# TopLevel.net
KiCad netlist of a schematic drawn in Altium Designer
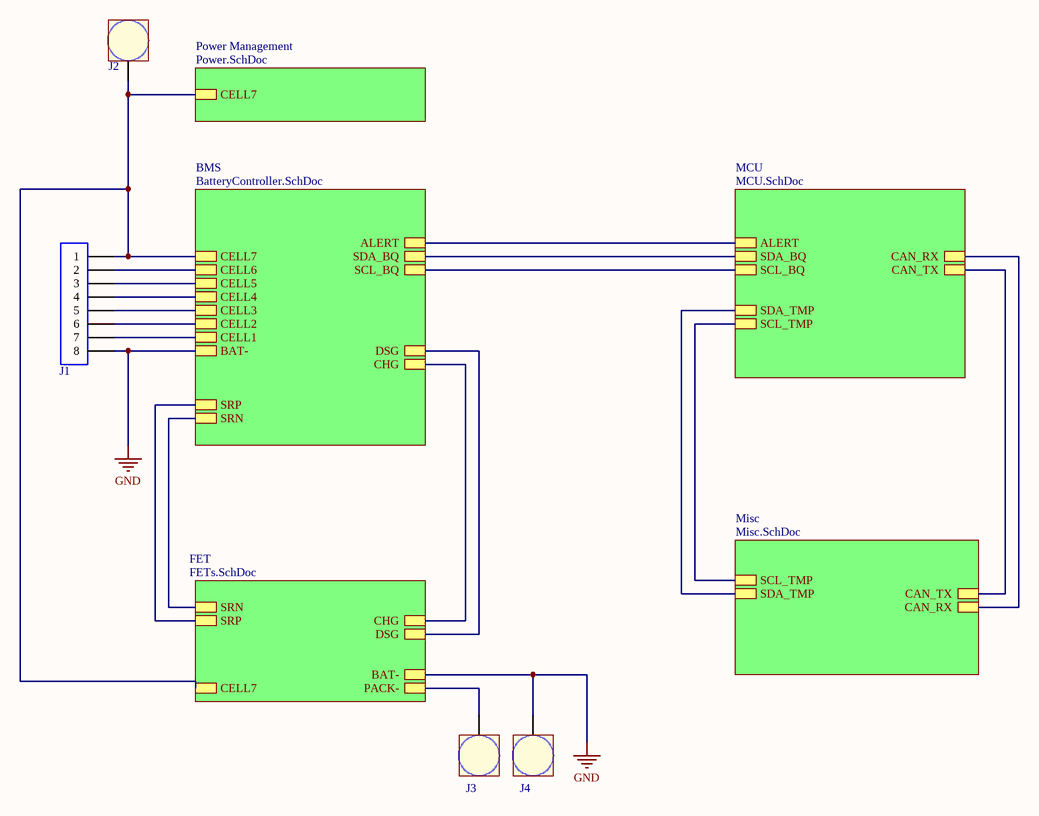
[diagram p0: TopLevel.SchDoc]

(export (version "E")
  (design (tool "Eeschema 10.0.6"))
  (components
    (comp (ref "J1")
      (value "HEADER-MALE-SMT-90C-4COL-2ROW")
      (footprint "0430450810")
      (description "Connector")
      (libsource (lib "Kaptanyums Lib") (part "0430450810"))
    )
    (comp (ref "J2")
      (value "7460305")
      (footprint "7460305")
      (description "Connector")
      (libsource (lib "Kaptanyums Lib") (part "7460305"))
    )
    (comp (ref "J3")
      (value "7460305")
      (footprint "7460305")
      (description "Connector")
      (libsource (lib "") (part "7460305_1"))
    )
    (comp (ref "J4")
      (value "7460305")
      (footprint "7460305")
      (description "Connector")
      (libsource (lib "") (part "7460305_1"))
    )
  )
  (nets
    (net (code "4") (name "/CELL1") (class "Default")
      (node (ref "J1") (pin "7") (pinfunction "7_7") (pintype "passive"))
    )
    (net (code "5") (name "/CELL2") (class "Default")
      (node (ref "J1") (pin "6") (pinfunction "6_6") (pintype "passive"))
    )
    (net (code "6") (name "/CELL3") (class "Default")
      (node (ref "J1") (pin "5") (pinfunction "5_5") (pintype "passive"))
    )
    (net (code "7") (name "/CELL4") (class "Default")
      (node (ref "J1") (pin "4") (pinfunction "4_4") (pintype "passive"))
    )
    (net (code "8") (name "/CELL5") (class "Default")
      (node (ref "J1") (pin "3") (pinfunction "3_3") (pintype "passive"))
    )
    (net (code "9") (name "/CELL6") (class "Default")
      (node (ref "J1") (pin "2") (pinfunction "2_2") (pintype "passive"))
    )
    (net (code "10") (name "/CELL7") (class "Default")
      (node (ref "J1") (pin "1") (pinfunction "1_1") (pintype "passive"))
      (node (ref "J2") (pin "1") (pinfunction "1_1") (pintype "passive"))
    )
    (net (code "13") (name "/PACK-") (class "Default")
      (node (ref "J3") (pin "1") (pinfunction "1_1") (pintype "passive"))
    )
    (net (code "20") (name "GND") (class "Default")
      (node (ref "J1") (pin "8") (pinfunction "8_8") (pintype "passive"))
      (node (ref "J4") (pin "1") (pinfunction "1_1") (pintype "passive"))
    )
  )
)
